# main_board3.net
KiCad netlist of a schematic drawn in EAGLE
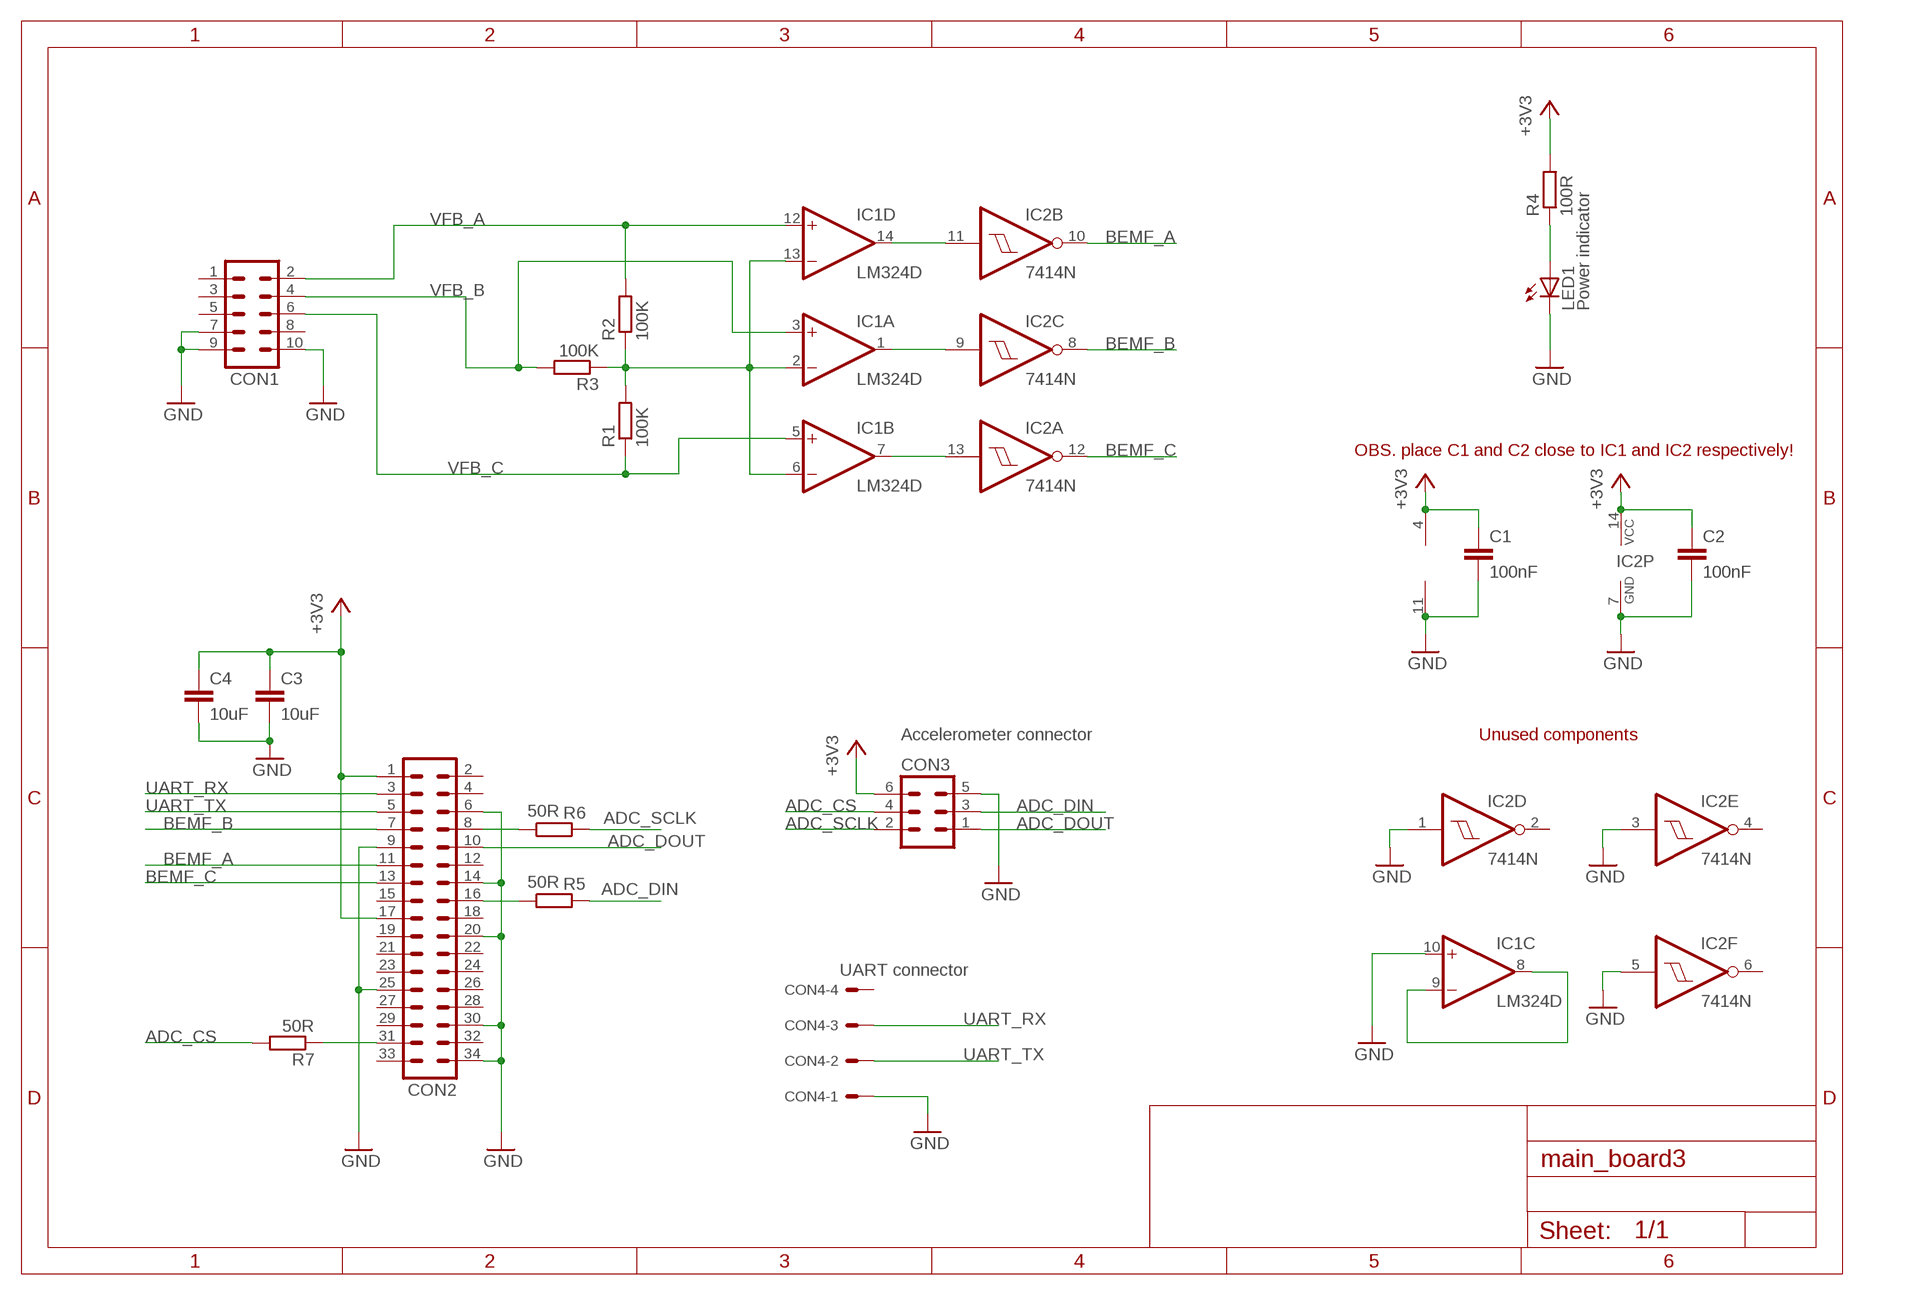
[diagram p0: schematic, sheet 1]

(export (version "E")
  (design (tool "Eeschema 10.0.6"))
  (components
    (comp (ref "C1")
      (value "100nF")
      (footprint "eagle-import:C0805K")
      (libsource (lib "eagle-import") (part "C-EUC0805K"))
    )
    (comp (ref "C2")
      (value "100nF")
      (footprint "eagle-import:C0805K")
      (libsource (lib "eagle-import") (part "C-EUC0805K"))
    )
    (comp (ref "C3")
      (value "10uF")
      (footprint "eagle-import:C1206K")
      (libsource (lib "eagle-import") (part "C-EUC1206K"))
    )
    (comp (ref "C4")
      (value "10uF")
      (footprint "eagle-import:C1206K")
      (libsource (lib "eagle-import") (part "C-EUC1206K"))
    )
    (comp (ref "CON1")
      (value "MA05-2")
      (footprint "eagle-import:MA05-2")
      (libsource (lib "eagle-import") (part "MA05-2"))
    )
    (comp (ref "CON2")
      (value "MA17-2")
      (footprint "eagle-import:MA17-2")
      (libsource (lib "eagle-import") (part "MA17-2"))
    )
    (comp (ref "CON3")
      (value "Accelerometer connector")
      (footprint "eagle-import:ML6")
      (libsource (lib "eagle-import") (part "ML6"))
    )
    (comp (ref "CON4")
      (value "UART connector")
      (footprint "eagle-import:6410-04")
      (libsource (lib "eagle-import") (part "22-?-0427-2041"))
    )
    (comp (ref "IC1")
      (value "LM324D")
      (footprint "eagle-import:SO14")
      (libsource (lib "eagle-import") (part "LM324D"))
    )
    (comp (ref "IC2")
      (value "7414N")
      (footprint "eagle-import:DIL14")
      (libsource (lib "eagle-import") (part "7414N"))
    )
    (comp (ref "LED1")
      (value "Power indicator")
      (footprint "eagle-import:CHIP-LED0805")
      (libsource (lib "eagle-import") (part "LEDCHIP-LED0805"))
    )
    (comp (ref "R1")
      (value "100K")
      (footprint "eagle-import:R0805")
      (libsource (lib "eagle-import") (part "R-EU_R0805"))
    )
    (comp (ref "R2")
      (value "100K")
      (footprint "eagle-import:R0805")
      (libsource (lib "eagle-import") (part "R-EU_R0805"))
    )
    (comp (ref "R3")
      (value "100K")
      (footprint "eagle-import:R0805")
      (libsource (lib "eagle-import") (part "R-EU_R0805"))
    )
    (comp (ref "R4")
      (value "100R")
      (footprint "eagle-import:R0805")
      (libsource (lib "eagle-import") (part "R-EU_R0805"))
    )
    (comp (ref "R5")
      (value "50R")
      (footprint "eagle-import:R0805")
      (libsource (lib "eagle-import") (part "R-EU_R0805"))
    )
    (comp (ref "R6")
      (value "50R")
      (footprint "eagle-import:R0805")
      (libsource (lib "eagle-import") (part "R-EU_R0805"))
    )
    (comp (ref "R7")
      (value "50R")
      (footprint "eagle-import:R0805")
      (libsource (lib "eagle-import") (part "R-EU_R0805"))
    )
  )
  (nets
    (net (code "1") (name "+3V3") (class "Default")
      (node (ref "C1") (pin "1") (pinfunction "1_1") (pintype "passive"))
      (node (ref "C2") (pin "1") (pinfunction "1_1") (pintype "passive"))
      (node (ref "C3") (pin "1") (pinfunction "1_1") (pintype "passive"))
      (node (ref "C4") (pin "1") (pinfunction "1_1") (pintype "passive"))
      (node (ref "CON2") (pin "1") (pinfunction "1_1") (pintype "passive"))
      (node (ref "CON2") (pin "17") (pinfunction "17_17") (pintype "passive"))
      (node (ref "CON3") (pin "6") (pinfunction "6_6") (pintype "passive"))
      (node (ref "IC1") (pin "4") (pinfunction "V+_4") (pintype "power_in"))
      (node (ref "IC2") (pin "14") (pinfunction "VCC_14") (pintype "power_in"))
      (node (ref "R4") (pin "2") (pinfunction "2_2") (pintype "passive"))
    )
    (net (code "2") (name "/ADC_CS") (class "Default")
      (node (ref "CON3") (pin "4") (pinfunction "4_4") (pintype "passive"))
      (node (ref "R7") (pin "2") (pinfunction "2_2") (pintype "passive"))
    )
    (net (code "3") (name "/ADC_DIN") (class "Default")
      (node (ref "CON3") (pin "3") (pinfunction "3_3") (pintype "passive"))
      (node (ref "R5") (pin "2") (pinfunction "2_2") (pintype "passive"))
    )
    (net (code "4") (name "/ADC_DOUT") (class "Default")
      (node (ref "CON2") (pin "10") (pinfunction "10_10") (pintype "passive"))
      (node (ref "CON3") (pin "1") (pinfunction "1_1") (pintype "passive"))
    )
    (net (code "5") (name "/ADC_SCLK") (class "Default")
      (node (ref "CON3") (pin "2") (pinfunction "2_2") (pintype "passive"))
      (node (ref "R6") (pin "2") (pinfunction "2_2") (pintype "passive"))
    )
    (net (code "6") (name "/BEMF_A") (class "Default")
      (node (ref "CON2") (pin "11") (pinfunction "11_11") (pintype "passive"))
      (node (ref "IC2") (pin "10") (pinfunction "O_10") (pintype "output"))
    )
    (net (code "7") (name "/BEMF_B") (class "Default")
      (node (ref "CON2") (pin "7") (pinfunction "7_7") (pintype "passive"))
      (node (ref "IC2") (pin "8") (pinfunction "O_8") (pintype "output"))
    )
    (net (code "8") (name "/BEMF_C") (class "Default")
      (node (ref "CON2") (pin "13") (pinfunction "13_13") (pintype "passive"))
      (node (ref "IC2") (pin "12") (pinfunction "O_12") (pintype "output"))
    )
    (net (code "9") (name "/UART_RX") (class "Default")
      (node (ref "CON2") (pin "3") (pinfunction "3_3") (pintype "passive"))
      (node (ref "CON4") (pin "3") (pinfunction "S_3") (pintype "passive"))
    )
    (net (code "10") (name "/UART_TX") (class "Default")
      (node (ref "CON2") (pin "5") (pinfunction "5_5") (pintype "passive"))
      (node (ref "CON4") (pin "2") (pinfunction "S_2") (pintype "passive"))
    )
    (net (code "11") (name "/VFB_A") (class "Default")
      (node (ref "CON1") (pin "2") (pinfunction "2_2") (pintype "passive"))
      (node (ref "IC1") (pin "12") (pinfunction "+IN_12") (pintype "input"))
      (node (ref "R2") (pin "2") (pinfunction "2_2") (pintype "passive"))
    )
    (net (code "12") (name "/VFB_B") (class "Default")
      (node (ref "CON1") (pin "4") (pinfunction "4_4") (pintype "passive"))
      (node (ref "IC1") (pin "3") (pinfunction "+IN_3") (pintype "input"))
      (node (ref "R3") (pin "2") (pinfunction "2_2") (pintype "passive"))
    )
    (net (code "13") (name "/VFB_C") (class "Default")
      (node (ref "CON1") (pin "6") (pinfunction "6_6") (pintype "passive"))
      (node (ref "IC1") (pin "5") (pinfunction "+IN_5") (pintype "input"))
      (node (ref "R1") (pin "1") (pinfunction "1_1") (pintype "passive"))
    )
    (net (code "14") (name "GND") (class "Default")
      (node (ref "C1") (pin "2") (pinfunction "2_2") (pintype "passive"))
      (node (ref "C2") (pin "2") (pinfunction "2_2") (pintype "passive"))
      (node (ref "C3") (pin "2") (pinfunction "2_2") (pintype "passive"))
      (node (ref "C4") (pin "2") (pinfunction "2_2") (pintype "passive"))
      (node (ref "CON1") (pin "10") (pinfunction "10_10") (pintype "passive"))
      (node (ref "CON1") (pin "7") (pinfunction "7_7") (pintype "passive"))
      (node (ref "CON1") (pin "9") (pinfunction "9_9") (pintype "passive"))
      (node (ref "CON2") (pin "14") (pinfunction "14_14") (pintype "passive"))
      (node (ref "CON2") (pin "20") (pinfunction "20_20") (pintype "passive"))
      (node (ref "CON2") (pin "25") (pinfunction "25_25") (pintype "passive"))
      (node (ref "CON2") (pin "30") (pinfunction "30_30") (pintype "passive"))
      (node (ref "CON2") (pin "34") (pinfunction "34_34") (pintype "passive"))
      (node (ref "CON2") (pin "6") (pinfunction "6_6") (pintype "passive"))
      (node (ref "CON2") (pin "9") (pinfunction "9_9") (pintype "passive"))
      (node (ref "CON3") (pin "5") (pinfunction "5_5") (pintype "passive"))
      (node (ref "CON4") (pin "1") (pinfunction "S_1") (pintype "passive"))
      (node (ref "IC1") (pin "10") (pinfunction "+IN_10") (pintype "input"))
      (node (ref "IC1") (pin "11") (pinfunction "V-_11") (pintype "power_in"))
      (node (ref "IC2") (pin "1") (pinfunction "I_1") (pintype "input"))
      (node (ref "IC2") (pin "3") (pinfunction "I_3") (pintype "input"))
      (node (ref "IC2") (pin "5") (pinfunction "I_5") (pintype "input"))
      (node (ref "IC2") (pin "7") (pinfunction "GND_7") (pintype "power_in"))
      (node (ref "LED1") (pin "C") (pinfunction "C_C") (pintype "passive"))
    )
    (net (code "15") (name "Net-(CON2-Pad8)") (class "Default")
      (node (ref "CON2") (pin "8") (pinfunction "8_8") (pintype "passive"))
      (node (ref "R6") (pin "1") (pinfunction "1_1") (pintype "passive"))
    )
    (net (code "16") (name "Net-(CON2-Pad16)") (class "Default")
      (node (ref "CON2") (pin "16") (pinfunction "16_16") (pintype "passive"))
      (node (ref "R5") (pin "1") (pinfunction "1_1") (pintype "passive"))
    )
    (net (code "17") (name "Net-(CON2-Pad31)") (class "Default")
      (node (ref "CON2") (pin "31") (pinfunction "31_31") (pintype "passive"))
      (node (ref "R7") (pin "1") (pinfunction "1_1") (pintype "passive"))
    )
    (net (code "18") (name "Net-(IC1A--IN)") (class "Default")
      (node (ref "IC1") (pin "13") (pinfunction "-IN_13") (pintype "input"))
      (node (ref "IC1") (pin "2") (pinfunction "-IN_2") (pintype "input"))
      (node (ref "IC1") (pin "6") (pinfunction "-IN_6") (pintype "input"))
      (node (ref "R1") (pin "2") (pinfunction "2_2") (pintype "passive"))
      (node (ref "R2") (pin "1") (pinfunction "1_1") (pintype "passive"))
      (node (ref "R3") (pin "1") (pinfunction "1_1") (pintype "passive"))
    )
    (net (code "19") (name "Net-(IC1A-OUT)") (class "Default")
      (node (ref "IC1") (pin "1") (pinfunction "OUT_1") (pintype "output"))
      (node (ref "IC2") (pin "9") (pinfunction "I_9") (pintype "input"))
    )
    (net (code "20") (name "Net-(IC1B-OUT)") (class "Default")
      (node (ref "IC1") (pin "7") (pinfunction "OUT_7") (pintype "output"))
      (node (ref "IC2") (pin "13") (pinfunction "I_13") (pintype "input"))
    )
    (net (code "21") (name "Net-(IC1C--IN)") (class "Default")
      (node (ref "IC1") (pin "8") (pinfunction "OUT_8") (pintype "output"))
      (node (ref "IC1") (pin "9") (pinfunction "-IN_9") (pintype "input"))
    )
    (net (code "22") (name "Net-(IC1D-OUT)") (class "Default")
      (node (ref "IC1") (pin "14") (pinfunction "OUT_14") (pintype "output"))
      (node (ref "IC2") (pin "11") (pinfunction "I_11") (pintype "input"))
    )
    (net (code "23") (name "Net-(LED1-PadA)") (class "Default")
      (node (ref "LED1") (pin "A") (pinfunction "A_A") (pintype "passive"))
      (node (ref "R4") (pin "1") (pinfunction "1_1") (pintype "passive"))
    )
    (net (code "24") (name "unconnected-(CON1-Pad1)") (class "Default")
      (node (ref "CON1") (pin "1") (pinfunction "1_1") (pintype "passive"))
    )
    (net (code "25") (name "unconnected-(CON1-Pad3)") (class "Default")
      (node (ref "CON1") (pin "3") (pinfunction "3_3") (pintype "passive"))
    )
    (net (code "26") (name "unconnected-(CON1-Pad5)") (class "Default")
      (node (ref "CON1") (pin "5") (pinfunction "5_5") (pintype "passive"))
    )
    (net (code "27") (name "unconnected-(CON1-Pad8)") (class "Default")
      (node (ref "CON1") (pin "8") (pinfunction "8_8") (pintype "passive"))
    )
    (net (code "28") (name "unconnected-(CON2-Pad2)") (class "Default")
      (node (ref "CON2") (pin "2") (pinfunction "2_2") (pintype "passive"))
    )
    (net (code "29") (name "unconnected-(CON2-Pad4)") (class "Default")
      (node (ref "CON2") (pin "4") (pinfunction "4_4") (pintype "passive"))
    )
    (net (code "30") (name "unconnected-(CON2-Pad12)") (class "Default")
      (node (ref "CON2") (pin "12") (pinfunction "12_12") (pintype "passive"))
    )
    (net (code "31") (name "unconnected-(CON2-Pad15)") (class "Default")
      (node (ref "CON2") (pin "15") (pinfunction "15_15") (pintype "passive"))
    )
    (net (code "32") (name "unconnected-(CON2-Pad18)") (class "Default")
      (node (ref "CON2") (pin "18") (pinfunction "18_18") (pintype "passive"))
    )
    (net (code "33") (name "unconnected-(CON2-Pad19)") (class "Default")
      (node (ref "CON2") (pin "19") (pinfunction "19_19") (pintype "passive"))
    )
    (net (code "34") (name "unconnected-(CON2-Pad21)") (class "Default")
      (node (ref "CON2") (pin "21") (pinfunction "21_21") (pintype "passive"))
    )
    (net (code "35") (name "unconnected-(CON2-Pad22)") (class "Default")
      (node (ref "CON2") (pin "22") (pinfunction "22_22") (pintype "passive"))
    )
    (net (code "36") (name "unconnected-(CON2-Pad23)") (class "Default")
      (node (ref "CON2") (pin "23") (pinfunction "23_23") (pintype "passive"))
    )
    (net (code "37") (name "unconnected-(CON2-Pad24)") (class "Default")
      (node (ref "CON2") (pin "24") (pinfunction "24_24") (pintype "passive"))
    )
    (net (code "38") (name "unconnected-(CON2-Pad26)") (class "Default")
      (node (ref "CON2") (pin "26") (pinfunction "26_26") (pintype "passive"))
    )
    (net (code "39") (name "unconnected-(CON2-Pad27)") (class "Default")
      (node (ref "CON2") (pin "27") (pinfunction "27_27") (pintype "passive"))
    )
    (net (code "40") (name "unconnected-(CON2-Pad28)") (class "Default")
      (node (ref "CON2") (pin "28") (pinfunction "28_28") (pintype "passive"))
    )
    (net (code "41") (name "unconnected-(CON2-Pad29)") (class "Default")
      (node (ref "CON2") (pin "29") (pinfunction "29_29") (pintype "passive"))
    )
    (net (code "42") (name "unconnected-(CON2-Pad32)") (class "Default")
      (node (ref "CON2") (pin "32") (pinfunction "32_32") (pintype "passive"))
    )
    (net (code "43") (name "unconnected-(CON2-Pad33)") (class "Default")
      (node (ref "CON2") (pin "33") (pinfunction "33_33") (pintype "passive"))
    )
    (net (code "44") (name "unconnected-(CON4D-S-Pad4)") (class "Default")
      (node (ref "CON4") (pin "4") (pinfunction "S_4") (pintype "passive"))
    )
    (net (code "45") (name "unconnected-(IC2D-O-Pad2)") (class "Default")
      (node (ref "IC2") (pin "2") (pinfunction "O_2") (pintype "output"))
    )
    (net (code "46") (name "unconnected-(IC2E-O-Pad4)") (class "Default")
      (node (ref "IC2") (pin "4") (pinfunction "O_4") (pintype "output"))
    )
    (net (code "47") (name "unconnected-(IC2F-O-Pad6)") (class "Default")
      (node (ref "IC2") (pin "6") (pinfunction "O_6") (pintype "output"))
    )
  )
)
